# untitled.net
KiCad netlist of a schematic drawn in EAGLE
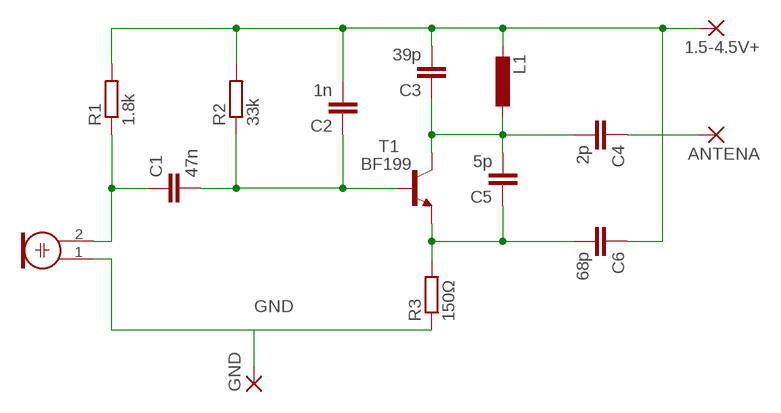
[diagram p0: schematic, sheet 1]

(export (version "E")
  (design (tool "Eeschema 10.0.6"))
  (components
    (comp (ref "1.5-4.5V+")
      (value "3,81/1,4")
      (footprint "eagle-import:3,81_1,4")
      (libsource (lib "eagle-import") (part "3,81/1,4"))
    )
    (comp (ref "ANTENA")
      (value "3,81/1,4")
      (footprint "eagle-import:3,81_1,4")
      (libsource (lib "eagle-import") (part "3,81/1,4"))
    )
    (comp (ref "C1")
      (value "47n")
      (footprint "eagle-import:C025-025X050")
      (libsource (lib "eagle-import") (part "C-EU025-025X050"))
    )
    (comp (ref "C2")
      (value "1n")
      (footprint "eagle-import:C025-025X050")
      (libsource (lib "eagle-import") (part "C-EU025-025X050"))
    )
    (comp (ref "C3")
      (value "39p")
      (footprint "eagle-import:C025-025X050")
      (libsource (lib "eagle-import") (part "C-EU025-025X050"))
    )
    (comp (ref "C4")
      (value "2p")
      (footprint "eagle-import:C025-025X050")
      (libsource (lib "eagle-import") (part "C-EU025-025X050"))
    )
    (comp (ref "C5")
      (value "5p")
      (footprint "eagle-import:C025-025X050")
      (libsource (lib "eagle-import") (part "C-EU025-025X050"))
    )
    (comp (ref "C6")
      (value "68p")
      (footprint "eagle-import:C025-025X050")
      (libsource (lib "eagle-import") (part "C-EU025-025X050"))
    )
    (comp (ref "GND")
      (value "3,81/1,4")
      (footprint "eagle-import:3,81_1,4")
      (libsource (lib "eagle-import") (part "3,81/1,4"))
    )
    (comp (ref "L1")
      (value "L-EU0207/7")
      (footprint "eagle-import:0207_7")
      (libsource (lib "eagle-import") (part "L-EU0207/7"))
    )
    (comp (ref "M1")
      (value "ELECTRET_MICROPHON-WM-61B")
      (footprint "eagle-import:WM-61B")
      (libsource (lib "eagle-import") (part "ELECTRET_MICROPHON-WM-61B"))
    )
    (comp (ref "R1")
      (value "1.8k")
      (footprint "eagle-import:0207_10")
      (libsource (lib "eagle-import") (part "R-EU_0207/10"))
    )
    (comp (ref "R2")
      (value "33k")
      (footprint "eagle-import:0207_10")
      (libsource (lib "eagle-import") (part "R-EU_0207/10"))
    )
    (comp (ref "R3")
      (value "150Ω")
      (footprint "eagle-import:0207_10")
      (libsource (lib "eagle-import") (part "R-EU_0207/10"))
    )
    (comp (ref "T1")
      (value "BF199")
      (footprint "eagle-import:TO92")
      (libsource (lib "eagle-import") (part "BF199"))
    )
  )
  (nets
    (net (code "1") (name "/GND") (class "Default")
      (node (ref "GND") (pin "1") (pinfunction "P_1") (pintype "passive"))
      (node (ref "M1") (pin "1") (pinfunction "1_1") (pintype "passive"))
      (node (ref "R3") (pin "1") (pinfunction "1_1") (pintype "passive"))
    )
    (net (code "2") (name "Net-(1.5-4.5V+-P)") (class "Default")
      (node (ref "1.5-4.5V+") (pin "1") (pinfunction "P_1") (pintype "passive"))
      (node (ref "C2") (pin "2") (pinfunction "2_2") (pintype "passive"))
      (node (ref "C3") (pin "2") (pinfunction "2_2") (pintype "passive"))
      (node (ref "C6") (pin "1") (pinfunction "1_1") (pintype "passive"))
      (node (ref "L1") (pin "2") (pinfunction "2_2") (pintype "passive"))
      (node (ref "R1") (pin "2") (pinfunction "2_2") (pintype "passive"))
      (node (ref "R2") (pin "2") (pinfunction "2_2") (pintype "passive"))
    )
    (net (code "3") (name "Net-(ANTENA-P)") (class "Default")
      (node (ref "ANTENA") (pin "1") (pinfunction "P_1") (pintype "passive"))
      (node (ref "C4") (pin "1") (pinfunction "1_1") (pintype "passive"))
    )
    (net (code "4") (name "Net-(C1-Pad1)") (class "Default")
      (node (ref "C1") (pin "1") (pinfunction "1_1") (pintype "passive"))
      (node (ref "M1") (pin "2") (pinfunction "2_2") (pintype "passive"))
      (node (ref "R1") (pin "1") (pinfunction "1_1") (pintype "passive"))
    )
    (net (code "5") (name "Net-(T1-B)") (class "Default")
      (node (ref "C1") (pin "2") (pinfunction "2_2") (pintype "passive"))
      (node (ref "C2") (pin "1") (pinfunction "1_1") (pintype "passive"))
      (node (ref "R2") (pin "1") (pinfunction "1_1") (pintype "passive"))
      (node (ref "T1") (pin "1") (pinfunction "B_1") (pintype "passive"))
    )
    (net (code "6") (name "Net-(T1-C)") (class "Default")
      (node (ref "C3") (pin "1") (pinfunction "1_1") (pintype "passive"))
      (node (ref "C4") (pin "2") (pinfunction "2_2") (pintype "passive"))
      (node (ref "C5") (pin "2") (pinfunction "2_2") (pintype "passive"))
      (node (ref "L1") (pin "1") (pinfunction "1_1") (pintype "passive"))
      (node (ref "T1") (pin "3") (pinfunction "C_3") (pintype "passive"))
    )
    (net (code "7") (name "Net-(T1-E)") (class "Default")
      (node (ref "C5") (pin "1") (pinfunction "1_1") (pintype "passive"))
      (node (ref "C6") (pin "2") (pinfunction "2_2") (pintype "passive"))
      (node (ref "R3") (pin "2") (pinfunction "2_2") (pintype "passive"))
      (node (ref "T1") (pin "2") (pinfunction "E_2") (pintype "passive"))
    )
  )
)
